# HC-001.net
KiCad netlist of a schematic drawn in Altium Designer
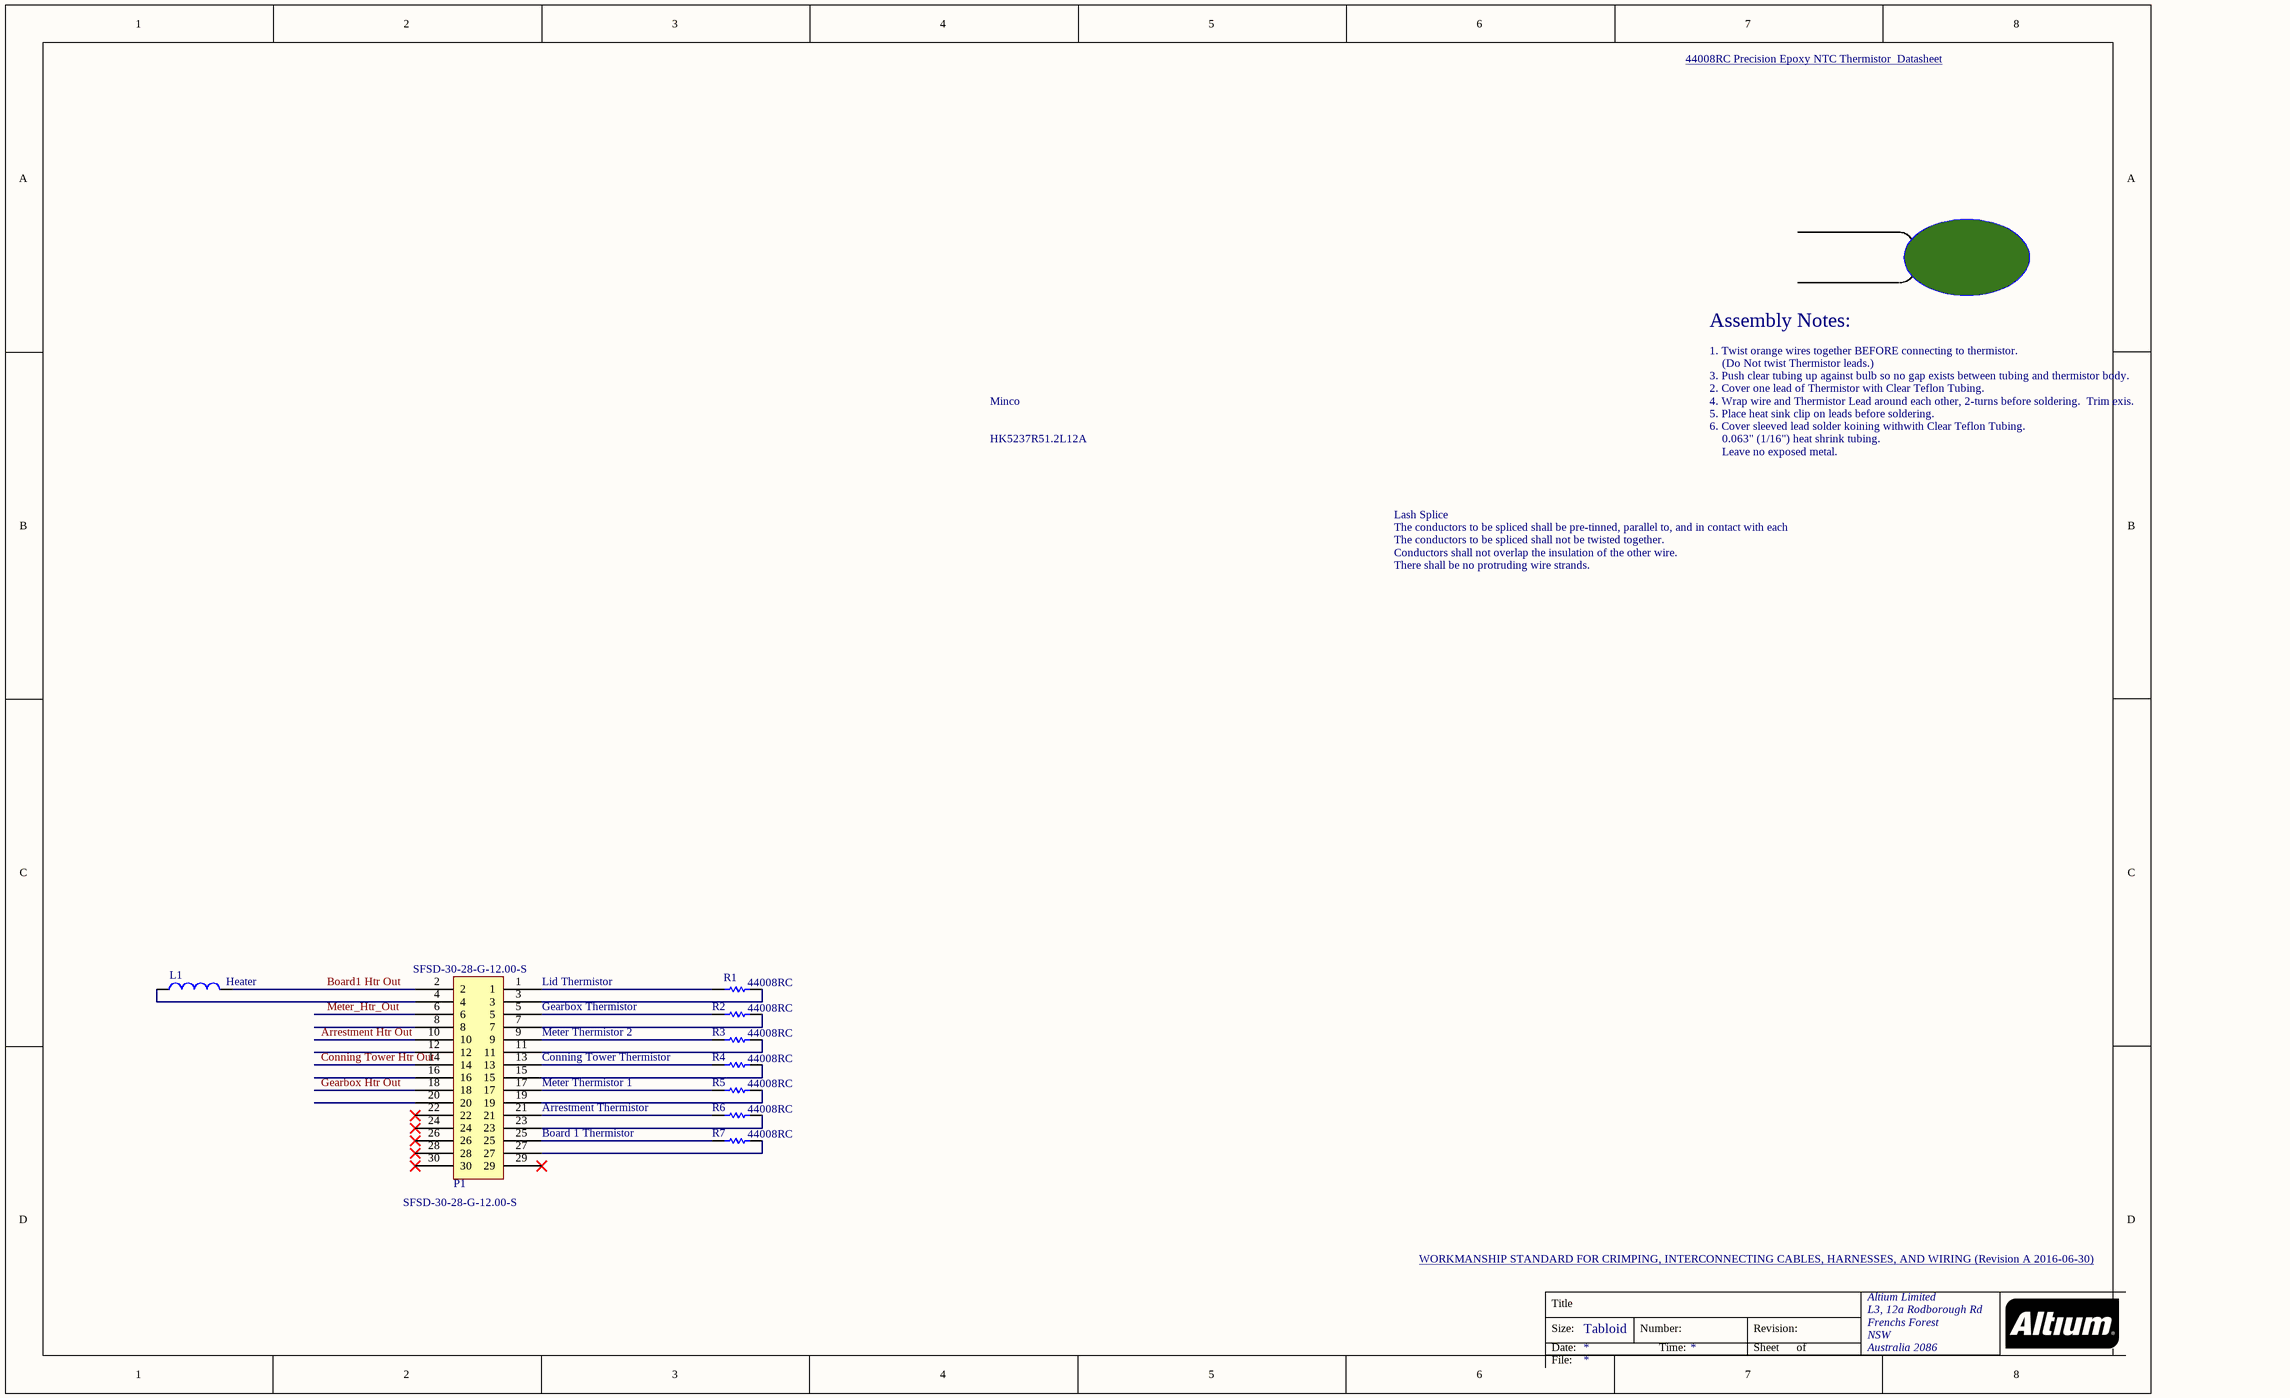
[diagram p0: HC-001.SchDoc]

(export (version "E")
  (design (tool "Eeschema 10.0.6"))
  (components
    (comp (ref "L1")
      (value "Heater")
      (footprint "0402-A")
      (fields
        (field (name "MANUFACTURER PART NUMBER") "HK5237R51.2L12A")
        (field (name "MANUFACTURER") "Minco")
      )
      (libsource (lib "Miscellaneous Devices") (part "Inductor"))
    )
    (comp (ref "P1")
      (value "SFSD-30-28-G-12.00-S")
      (footprint "SFSD-30-28")
      (description "60 Position Cable Assembly Rectangular Socket to Individual Wire Leads 1.00' (304.80mm)")
      (fields
        (field (name "MANUFACTURER") "Samtec")
        (field (name "MANUFACTURER PART NUMBER") "SFSD-30-28-H-10.00-SR")
      )
      (libsource (lib "ZLS_Schematic_lib") (part "TFM-115-01-L-D-RE2-WT"))
    )
    (comp (ref "R1")
      (value "44008RC")
      (footprint "RESC0805(2012)_N")
      (fields (field (name "MANUFACTURER") "Measurement Specialties") (field (name "TOLERANCE") "0.8%"))
      (libsource (lib "Altium Content Vault") (part "CMP-1013-00606-1"))
    )
    (comp (ref "R2")
      (value "44008RC")
      (footprint "RESC0805(2012)_N")
      (fields (field (name "MANUFACTURER") "Measurement Specialties") (field (name "TOLERANCE") "0.8%"))
      (libsource (lib "Altium Content Vault") (part "CMP-1013-00606-1"))
    )
    (comp (ref "R3")
      (value "44008RC")
      (footprint "RESC0805(2012)_N")
      (fields (field (name "MANUFACTURER") "Measurement Specialties") (field (name "TOLERANCE") "0.8%"))
      (libsource (lib "Altium Content Vault") (part "CMP-1013-00606-1"))
    )
    (comp (ref "R4")
      (value "44008RC")
      (footprint "RESC0805(2012)_N")
      (fields (field (name "MANUFACTURER") "Measurement Specialties") (field (name "TOLERANCE") "0.8%"))
      (libsource (lib "Altium Content Vault") (part "CMP-1013-00606-1"))
    )
    (comp (ref "R5")
      (value "44008RC")
      (footprint "RESC0805(2012)_N")
      (fields (field (name "MANUFACTURER") "Measurement Specialties") (field (name "TOLERANCE") "0.8%"))
      (libsource (lib "Altium Content Vault") (part "CMP-1013-00606-1"))
    )
    (comp (ref "R6")
      (value "44008RC")
      (footprint "RESC0805(2012)_N")
      (fields (field (name "MANUFACTURER") "Measurement Specialties") (field (name "TOLERANCE") "0.8%"))
      (libsource (lib "Altium Content Vault") (part "CMP-1013-00606-1"))
    )
    (comp (ref "R7")
      (value "44008RC")
      (footprint "RESC0805(2012)_N")
      (fields (field (name "MANUFACTURER") "Measurement Specialties") (field (name "TOLERANCE") "0.8%"))
      (libsource (lib "Altium Content Vault") (part "CMP-1013-00606-1"))
    )
  )
  (nets
    (net (code "1") (name "/Arrestment Htr Out") (class "Default")
      (node (ref "P1") (pin "10") (pinfunction "10_10") (pintype "passive"))
    )
    (net (code "2") (name "/Board1 Htr Out") (class "Default")
      (node (ref "L1") (pin "2") (pinfunction "2_2") (pintype "passive"))
      (node (ref "P1") (pin "2") (pinfunction "2_2") (pintype "passive"))
    )
    (net (code "3") (name "/Conning Tower Htr Out") (class "Default")
      (node (ref "P1") (pin "14") (pinfunction "14_14") (pintype "passive"))
    )
    (net (code "4") (name "/Gearbox Htr Out") (class "Default")
      (node (ref "P1") (pin "18") (pinfunction "18_18") (pintype "passive"))
    )
    (net (code "5") (name "/Meter_Htr_Out") (class "Default")
      (node (ref "P1") (pin "6") (pinfunction "6_6") (pintype "passive"))
    )
    (net (code "6") (name "Net-(L1-Pad1)") (class "Default")
      (node (ref "L1") (pin "1") (pinfunction "1_1") (pintype "passive"))
      (node (ref "P1") (pin "4") (pinfunction "4_4") (pintype "passive"))
    )
    (net (code "7") (name "Net-(P1-Pad1)") (class "Default")
      (node (ref "P1") (pin "1") (pinfunction "1_1") (pintype "passive"))
      (node (ref "R1") (pin "1") (pinfunction "1_1") (pintype "passive"))
    )
    (net (code "8") (name "Net-(P1-Pad3)") (class "Default")
      (node (ref "P1") (pin "3") (pinfunction "3_3") (pintype "passive"))
      (node (ref "R1") (pin "2") (pinfunction "2_2") (pintype "passive"))
    )
    (net (code "9") (name "Net-(P1-Pad5)") (class "Default")
      (node (ref "P1") (pin "5") (pinfunction "5_5") (pintype "passive"))
      (node (ref "R2") (pin "1") (pinfunction "1_1") (pintype "passive"))
    )
    (net (code "10") (name "Net-(P1-Pad7)") (class "Default")
      (node (ref "P1") (pin "7") (pinfunction "7_7") (pintype "passive"))
      (node (ref "R2") (pin "2") (pinfunction "2_2") (pintype "passive"))
    )
    (net (code "11") (name "Net-(P1-Pad9)") (class "Default")
      (node (ref "P1") (pin "9") (pinfunction "9_9") (pintype "passive"))
      (node (ref "R3") (pin "1") (pinfunction "1_1") (pintype "passive"))
    )
    (net (code "12") (name "Net-(P1-Pad11)") (class "Default")
      (node (ref "P1") (pin "11") (pinfunction "11_11") (pintype "passive"))
      (node (ref "R3") (pin "2") (pinfunction "2_2") (pintype "passive"))
    )
    (net (code "13") (name "Net-(P1-Pad13)") (class "Default")
      (node (ref "P1") (pin "13") (pinfunction "13_13") (pintype "passive"))
      (node (ref "R4") (pin "1") (pinfunction "1_1") (pintype "passive"))
    )
    (net (code "14") (name "Net-(P1-Pad15)") (class "Default")
      (node (ref "P1") (pin "15") (pinfunction "15_15") (pintype "passive"))
      (node (ref "R4") (pin "2") (pinfunction "2_2") (pintype "passive"))
    )
    (net (code "15") (name "Net-(P1-Pad17)") (class "Default")
      (node (ref "P1") (pin "17") (pinfunction "17_17") (pintype "passive"))
      (node (ref "R5") (pin "1") (pinfunction "1_1") (pintype "passive"))
    )
    (net (code "16") (name "Net-(P1-Pad19)") (class "Default")
      (node (ref "P1") (pin "19") (pinfunction "19_19") (pintype "passive"))
      (node (ref "R5") (pin "2") (pinfunction "2_2") (pintype "passive"))
    )
    (net (code "17") (name "Net-(P1-Pad21)") (class "Default")
      (node (ref "P1") (pin "21") (pinfunction "21_21") (pintype "passive"))
      (node (ref "R6") (pin "1") (pinfunction "1_1") (pintype "passive"))
    )
    (net (code "18") (name "Net-(P1-Pad23)") (class "Default")
      (node (ref "P1") (pin "23") (pinfunction "23_23") (pintype "passive"))
      (node (ref "R6") (pin "2") (pinfunction "2_2") (pintype "passive"))
    )
    (net (code "19") (name "Net-(P1-Pad25)") (class "Default")
      (node (ref "P1") (pin "25") (pinfunction "25_25") (pintype "passive"))
      (node (ref "R7") (pin "1") (pinfunction "1_1") (pintype "passive"))
    )
    (net (code "20") (name "Net-(P1-Pad27)") (class "Default")
      (node (ref "P1") (pin "27") (pinfunction "27_27") (pintype "passive"))
      (node (ref "R7") (pin "2") (pinfunction "2_2") (pintype "passive"))
    )
    (net (code "21") (name "unconnected-(P1-Pad8)") (class "Default")
      (node (ref "P1") (pin "8") (pinfunction "8_8") (pintype "passive"))
    )
    (net (code "22") (name "unconnected-(P1-Pad12)") (class "Default")
      (node (ref "P1") (pin "12") (pinfunction "12_12") (pintype "passive"))
    )
    (net (code "23") (name "unconnected-(P1-Pad16)") (class "Default")
      (node (ref "P1") (pin "16") (pinfunction "16_16") (pintype "passive"))
    )
    (net (code "24") (name "unconnected-(P1-Pad20)") (class "Default")
      (node (ref "P1") (pin "20") (pinfunction "20_20") (pintype "passive"))
    )
    (net (code "25") (name "unconnected-(P1-Pad22)") (class "Default")
      (node (ref "P1") (pin "22") (pinfunction "22_22") (pintype "passive+no_connect"))
    )
    (net (code "26") (name "unconnected-(P1-Pad24)") (class "Default")
      (node (ref "P1") (pin "24") (pinfunction "24_24") (pintype "passive+no_connect"))
    )
    (net (code "27") (name "unconnected-(P1-Pad26)") (class "Default")
      (node (ref "P1") (pin "26") (pinfunction "26_26") (pintype "passive+no_connect"))
    )
    (net (code "28") (name "unconnected-(P1-Pad28)") (class "Default")
      (node (ref "P1") (pin "28") (pinfunction "28_28") (pintype "passive+no_connect"))
    )
    (net (code "29") (name "unconnected-(P1-Pad29)") (class "Default")
      (node (ref "P1") (pin "29") (pinfunction "29_29") (pintype "passive+no_connect"))
    )
    (net (code "30") (name "unconnected-(P1-Pad30)") (class "Default")
      (node (ref "P1") (pin "30") (pinfunction "30_30") (pintype "passive+no_connect"))
    )
  )
)
